# EncoderHeader.net
KiCad netlist of a schematic drawn in Altium Designer
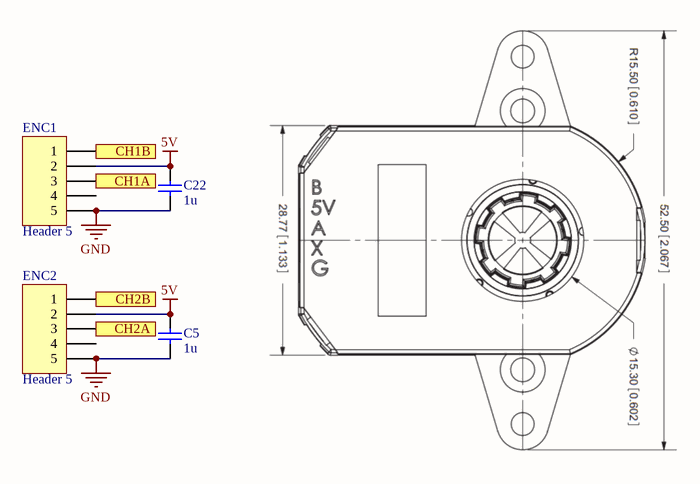
[diagram p0: EncoderHeader.SchDoc]

(export (version "E")
  (design (tool "Eeschema 10.0.6"))
  (components
    (comp (ref "C5")
      (value "1u")
      (footprint "CAPC1608X90N")
      (description "Capacitor")
      (fields (field (name "Comment") "Cap") (field (name "PUBLISHER") "Altium Limited"))
      (libsource (lib "IOBoard_Low") (part "Cap"))
    )
    (comp (ref "C22")
      (value "1u")
      (footprint "CAPC1608X90N")
      (description "Capacitor")
      (fields (field (name "Comment") "Cap") (field (name "PUBLISHER") "Altium Limited"))
      (libsource (lib "IOBoard_Low") (part "Cap"))
    )
    (comp (ref "ENC1")
      (value "Header 5")
      (footprint "HDR1X5")
      (description "Header, 5-Pin")
      (fields (field (name "PUBLISHER") "Altium Limited"))
      (libsource (lib "Miscellaneous Connectors") (part "Header 5"))
    )
    (comp (ref "ENC2")
      (value "Header 5")
      (footprint "HDR1X5")
      (description "Header, 5-Pin")
      (fields (field (name "PUBLISHER") "Altium Limited"))
      (libsource (lib "Miscellaneous Connectors") (part "Header 5"))
    )
  )
  (nets
    (net (code "1") (name "/CH1A") (class "Default")
      (node (ref "ENC1") (pin "3") (pinfunction "3_3") (pintype "passive"))
    )
    (net (code "2") (name "/CH1B") (class "Default")
      (node (ref "ENC1") (pin "1") (pinfunction "1_1") (pintype "passive"))
    )
    (net (code "3") (name "/CH2A") (class "Default")
      (node (ref "ENC2") (pin "3") (pinfunction "3_3") (pintype "passive"))
    )
    (net (code "4") (name "/CH2B") (class "Default")
      (node (ref "ENC2") (pin "1") (pinfunction "1_1") (pintype "passive"))
    )
    (net (code "5") (name "5V") (class "Default")
      (node (ref "C22") (pin "2") (pinfunction "2_2") (pintype "passive"))
      (node (ref "C5") (pin "2") (pinfunction "2_2") (pintype "passive"))
      (node (ref "ENC1") (pin "2") (pinfunction "2_2") (pintype "passive"))
      (node (ref "ENC2") (pin "2") (pinfunction "2_2") (pintype "passive"))
    )
    (net (code "6") (name "GND") (class "Default")
      (node (ref "C22") (pin "1") (pinfunction "1_1") (pintype "passive"))
      (node (ref "C5") (pin "1") (pinfunction "1_1") (pintype "passive"))
      (node (ref "ENC1") (pin "5") (pinfunction "5_5") (pintype "passive"))
      (node (ref "ENC2") (pin "5") (pinfunction "5_5") (pintype "passive"))
    )
    (net (code "7") (name "unconnected-(ENC1-Pad4)") (class "Default")
      (node (ref "ENC1") (pin "4") (pinfunction "4_4") (pintype "passive"))
    )
    (net (code "8") (name "unconnected-(ENC2-Pad4)") (class "Default")
      (node (ref "ENC2") (pin "4") (pinfunction "4_4") (pintype "passive"))
    )
  )
)
